# main.net
KiCad netlist of a schematic drawn in EAGLE
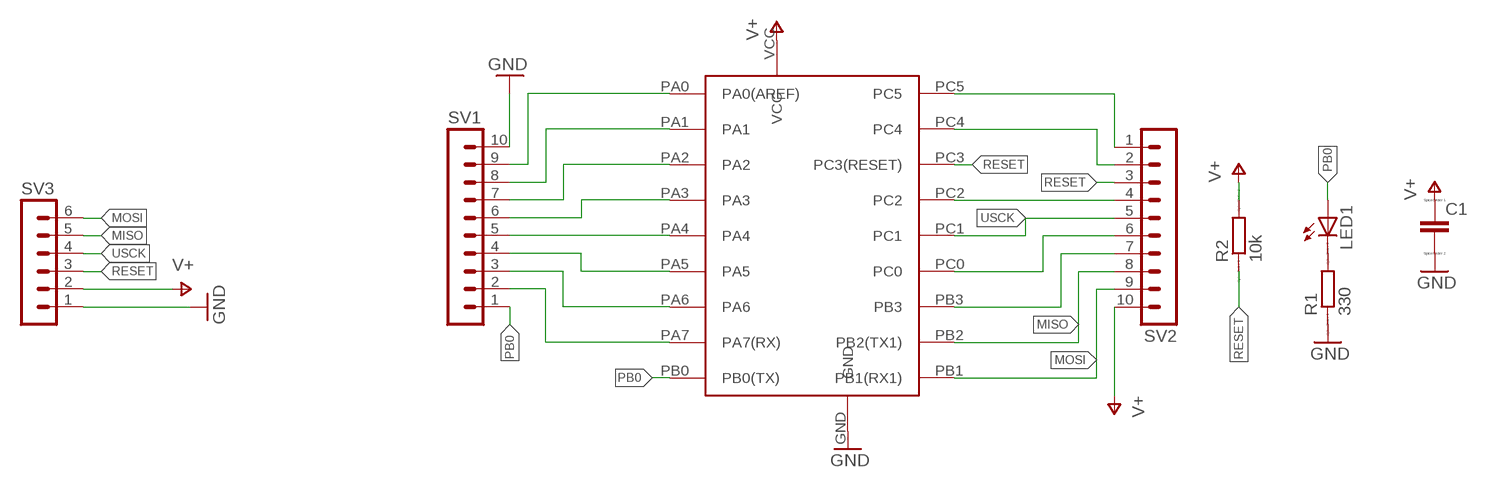
[diagram p0: schematic, sheet 1]

(export (version "E")
  (design (tool "Eeschema 10.0.6"))
  (components
    (comp (ref "C1")
      (value "CC0603")
      (footprint "eagle-import:C0603")
      (libsource (lib "eagle-import") (part "CC0603"))
    )
    (comp (ref "LED1")
      (value "LEDCHIP-LED0603")
      (footprint "eagle-import:CHIP-LED0603")
      (libsource (lib "eagle-import") (part "LEDCHIP-LED0603"))
    )
    (comp (ref "R1")
      (value "330")
      (footprint "eagle-import:R0603")
      (libsource (lib "eagle-import") (part "RR0603"))
    )
    (comp (ref "R2")
      (value "10k")
      (footprint "eagle-import:R0603")
      (libsource (lib "eagle-import") (part "RR0603"))
    )
    (comp (ref "SV1")
      (value "MA10-1")
      (footprint "eagle-import:MA10-1")
      (libsource (lib "eagle-import") (part "MA10-1"))
    )
    (comp (ref "SV2")
      (value "MA10-1")
      (footprint "eagle-import:MA10-1")
      (libsource (lib "eagle-import") (part "MA10-1"))
    )
    (comp (ref "SV3")
      (value "MA06-1")
      (footprint "eagle-import:MA06-1")
      (libsource (lib "eagle-import") (part "MA06-1"))
    )
    (comp (ref "U$1")
      (value "ATTINY1634")
      (footprint "eagle-import:SOIC20")
      (libsource (lib "eagle-import") (part "ATTINY1634"))
    )
  )
  (nets
    (net (code "1") (name "GND") (class "Default")
      (node (ref "C1") (pin "2") (pinfunction "2_2") (pintype "passive"))
      (node (ref "R1") (pin "1") (pinfunction "1_1") (pintype "passive"))
      (node (ref "SV1") (pin "10") (pinfunction "10_10") (pintype "passive"))
      (node (ref "SV3") (pin "1") (pinfunction "1_1") (pintype "passive"))
      (node (ref "U$1") (pin "GND") (pinfunction "GND_GND") (pintype "bidirectional"))
    )
    (net (code "2") (name "MISO") (class "Default")
      (node (ref "SV2") (pin "8") (pinfunction "8_8") (pintype "passive"))
      (node (ref "SV3") (pin "5") (pinfunction "5_5") (pintype "passive"))
      (node (ref "U$1") (pin "PB2") (pinfunction "PB2(TX1)_PB2") (pintype "bidirectional"))
    )
    (net (code "3") (name "MOSI") (class "Default")
      (node (ref "SV2") (pin "9") (pinfunction "9_9") (pintype "passive"))
      (node (ref "SV3") (pin "6") (pinfunction "6_6") (pintype "passive"))
      (node (ref "U$1") (pin "PB1") (pinfunction "PB1(RX1)_PB1") (pintype "bidirectional"))
    )
    (net (code "4") (name "Net-(LED1-PadC)") (class "Default")
      (node (ref "LED1") (pin "C") (pinfunction "C_C") (pintype "passive"))
      (node (ref "R1") (pin "2") (pinfunction "2_2") (pintype "passive"))
    )
    (net (code "5") (name "Net-(SV1-Pad3)") (class "Default")
      (node (ref "SV1") (pin "3") (pinfunction "3_3") (pintype "passive"))
      (node (ref "U$1") (pin "PA6") (pinfunction "PA6_PA6") (pintype "bidirectional"))
    )
    (net (code "6") (name "Net-(SV1-Pad4)") (class "Default")
      (node (ref "SV1") (pin "4") (pinfunction "4_4") (pintype "passive"))
      (node (ref "U$1") (pin "PA5") (pinfunction "PA5_PA5") (pintype "bidirectional"))
    )
    (net (code "7") (name "Net-(SV1-Pad5)") (class "Default")
      (node (ref "SV1") (pin "5") (pinfunction "5_5") (pintype "passive"))
      (node (ref "U$1") (pin "PA4") (pinfunction "PA4_PA4") (pintype "bidirectional"))
    )
    (net (code "8") (name "Net-(SV1-Pad6)") (class "Default")
      (node (ref "SV1") (pin "6") (pinfunction "6_6") (pintype "passive"))
      (node (ref "U$1") (pin "PA3") (pinfunction "PA3_PA3") (pintype "bidirectional"))
    )
    (net (code "9") (name "Net-(SV1-Pad7)") (class "Default")
      (node (ref "SV1") (pin "7") (pinfunction "7_7") (pintype "passive"))
      (node (ref "U$1") (pin "PA2") (pinfunction "PA2_PA2") (pintype "bidirectional"))
    )
    (net (code "10") (name "Net-(SV1-Pad8)") (class "Default")
      (node (ref "SV1") (pin "8") (pinfunction "8_8") (pintype "passive"))
      (node (ref "U$1") (pin "PA1") (pinfunction "PA1_PA1") (pintype "bidirectional"))
    )
    (net (code "11") (name "Net-(SV2-Pad1)") (class "Default")
      (node (ref "SV2") (pin "1") (pinfunction "1_1") (pintype "passive"))
      (node (ref "U$1") (pin "PC5") (pinfunction "PC5_PC5") (pintype "bidirectional"))
    )
    (net (code "12") (name "Net-(SV2-Pad2)") (class "Default")
      (node (ref "SV2") (pin "2") (pinfunction "2_2") (pintype "passive"))
      (node (ref "U$1") (pin "PC4") (pinfunction "PC4_PC4") (pintype "bidirectional"))
    )
    (net (code "13") (name "Net-(SV2-Pad4)") (class "Default")
      (node (ref "SV2") (pin "4") (pinfunction "4_4") (pintype "passive"))
      (node (ref "U$1") (pin "PC2") (pinfunction "PC2_PC2") (pintype "bidirectional"))
    )
    (net (code "14") (name "Net-(SV2-Pad6)") (class "Default")
      (node (ref "SV2") (pin "6") (pinfunction "6_6") (pintype "passive"))
      (node (ref "U$1") (pin "PC0") (pinfunction "PC0_PC0") (pintype "bidirectional"))
    )
    (net (code "15") (name "Net-(SV2-Pad7)") (class "Default")
      (node (ref "SV2") (pin "7") (pinfunction "7_7") (pintype "passive"))
      (node (ref "U$1") (pin "PB3") (pinfunction "PB3_PB3") (pintype "bidirectional"))
    )
    (net (code "16") (name "Net-(U$1-PA0(AREF))") (class "Default")
      (node (ref "SV1") (pin "9") (pinfunction "9_9") (pintype "passive"))
      (node (ref "U$1") (pin "PA0") (pinfunction "PA0(AREF)_PA0") (pintype "bidirectional"))
    )
    (net (code "17") (name "Net-(U$1-PA7(RX))") (class "Default")
      (node (ref "SV1") (pin "2") (pinfunction "2_2") (pintype "passive"))
      (node (ref "U$1") (pin "PA7") (pinfunction "PA7(RX)_PA7") (pintype "bidirectional"))
    )
    (net (code "18") (name "PB0") (class "Default")
      (node (ref "LED1") (pin "A") (pinfunction "A_A") (pintype "passive"))
      (node (ref "SV1") (pin "1") (pinfunction "1_1") (pintype "passive"))
      (node (ref "U$1") (pin "PB0") (pinfunction "PB0(TX)_PB0") (pintype "bidirectional"))
    )
    (net (code "19") (name "RESET") (class "Default")
      (node (ref "R2") (pin "1") (pinfunction "1_1") (pintype "passive"))
      (node (ref "SV2") (pin "3") (pinfunction "3_3") (pintype "passive"))
      (node (ref "SV3") (pin "3") (pinfunction "3_3") (pintype "passive"))
      (node (ref "U$1") (pin "PC3") (pinfunction "PC3(RESET)_PC3") (pintype "bidirectional"))
    )
    (net (code "20") (name "USCK") (class "Default")
      (node (ref "SV2") (pin "5") (pinfunction "5_5") (pintype "passive"))
      (node (ref "SV3") (pin "4") (pinfunction "4_4") (pintype "passive"))
      (node (ref "U$1") (pin "PC1") (pinfunction "PC1_PC1") (pintype "bidirectional"))
    )
    (net (code "21") (name "V+") (class "Default")
      (node (ref "C1") (pin "1") (pinfunction "1_1") (pintype "passive"))
      (node (ref "R2") (pin "2") (pinfunction "2_2") (pintype "passive"))
      (node (ref "SV2") (pin "10") (pinfunction "10_10") (pintype "passive"))
      (node (ref "SV3") (pin "2") (pinfunction "2_2") (pintype "passive"))
      (node (ref "U$1") (pin "VCC") (pinfunction "VCC_VCC") (pintype "bidirectional"))
    )
  )
)
